# version1.net
KiCad netlist of a schematic drawn in EAGLE
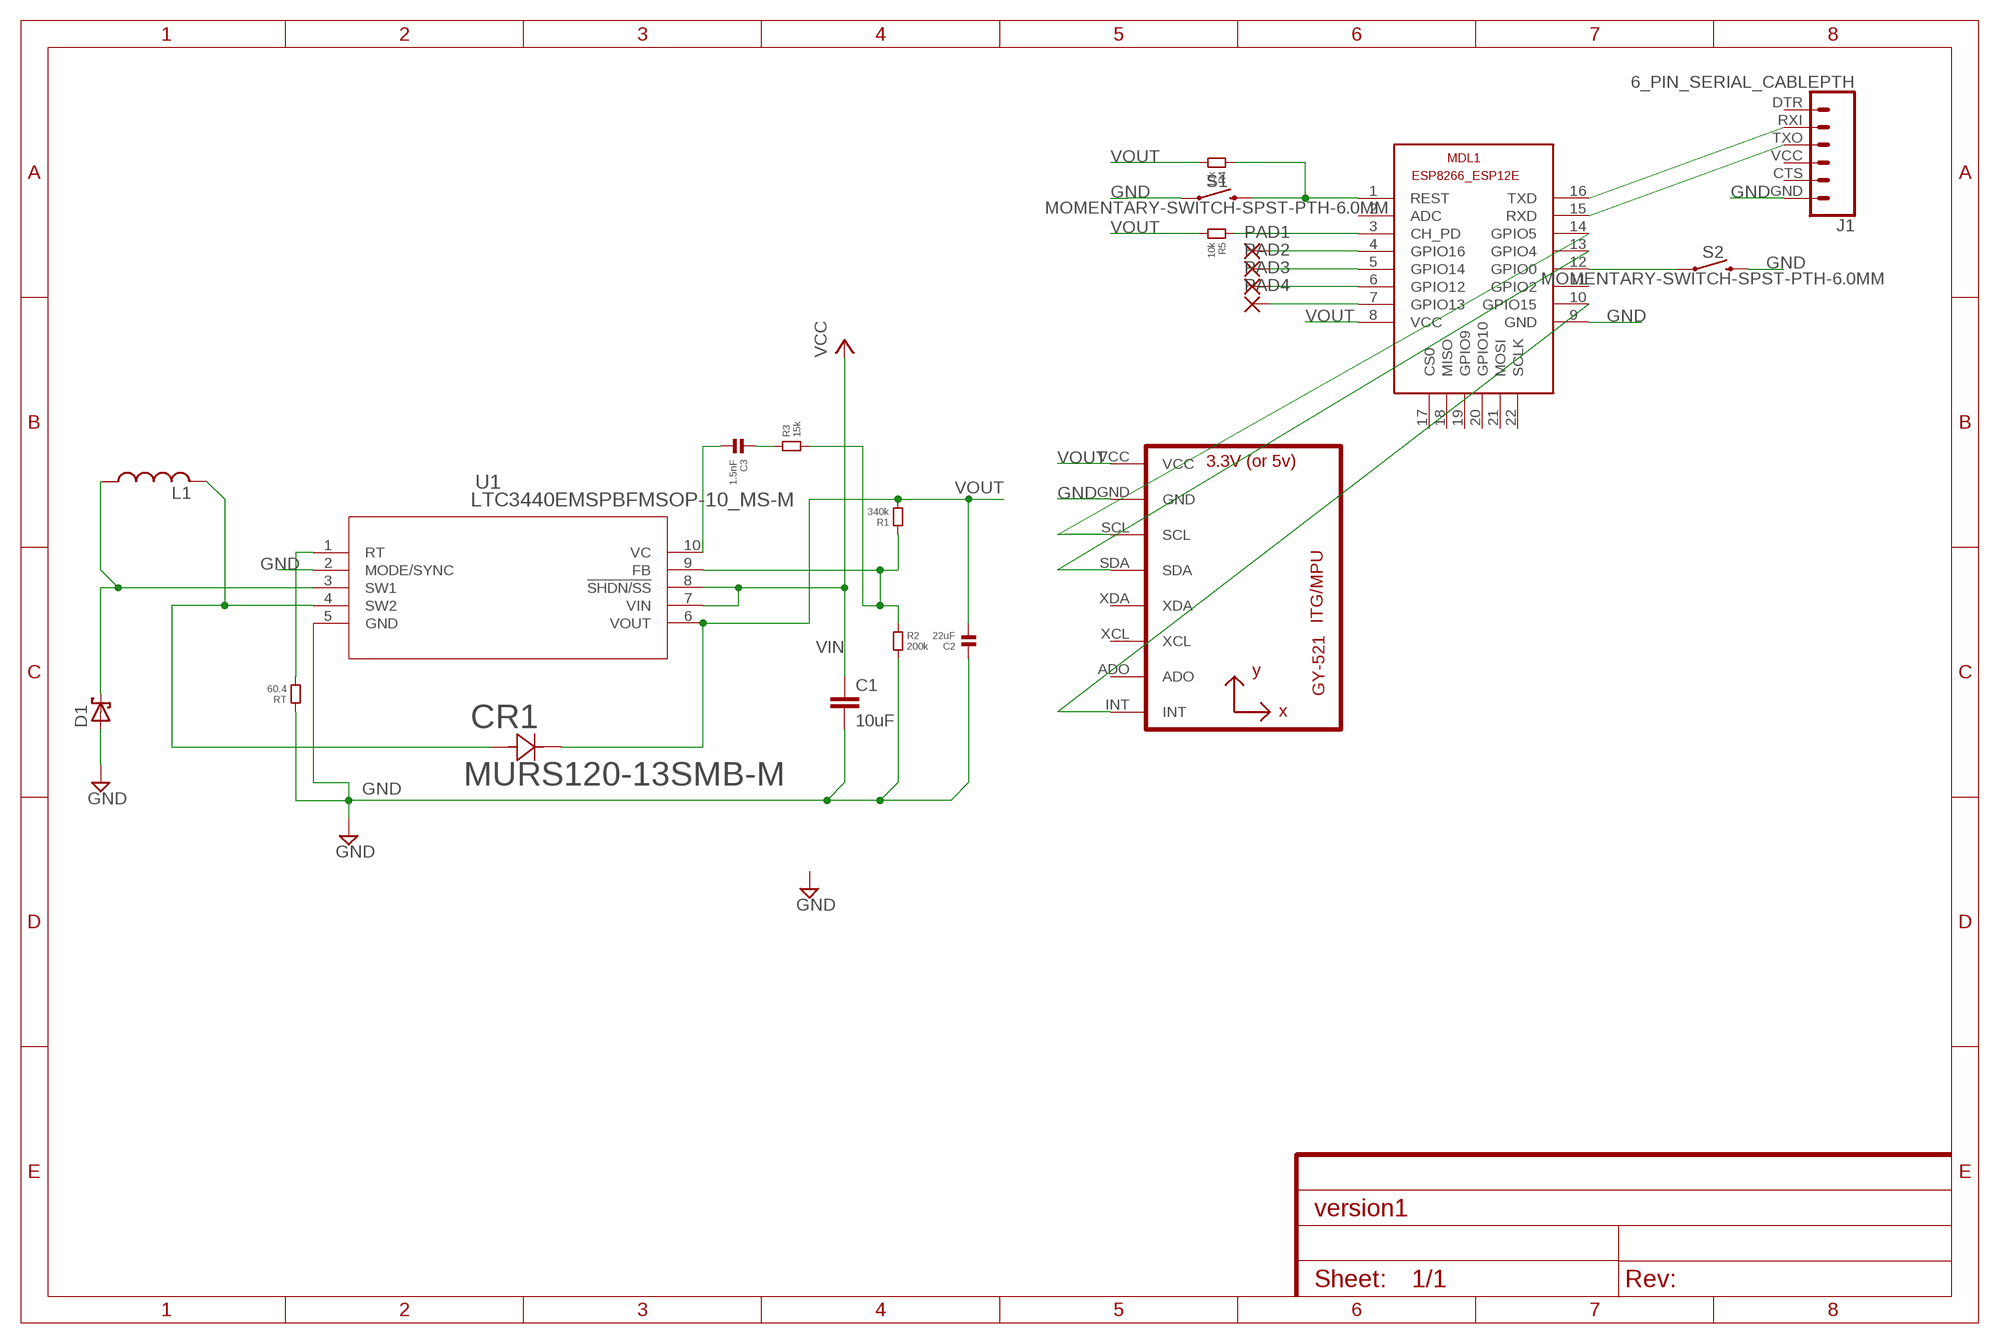
[diagram p0: schematic, sheet 1]

(export (version "E")
  (design (tool "Eeschema 10.0.6"))
  (components
    (comp (ref "C1")
      (value "10uF")
      (footprint "eagle-import:1206")
      (libsource (lib "eagle-import") (part "10UF-1206-6.3V-20%"))
    )
    (comp (ref "C2")
      (value "22uF")
      (footprint "eagle-import:1206")
      (libsource (lib "eagle-import") (part "CAPACITOR.1206"))
    )
    (comp (ref "C3")
      (value "1.5nF")
      (footprint "eagle-import:1206")
      (libsource (lib "eagle-import") (part "CAPACITOR.1206"))
    )
    (comp (ref "CR1")
      (value "MURS120-13SMB-M")
      (footprint "eagle-import:SMB-M")
      (fields (field (name "MANUFACTURER_PART_NUMBER") "MURS12013"))
      (libsource (lib "eagle-import") (part "MURS120-13SMB-M"))
    )
    (comp (ref "D1")
      (value "SCHOTTKY-DIODEDFLS130L-7")
      (footprint "eagle-import:POWERDI-123")
      (fields (field (name "MF") "Diodes Inc") (field (name "MPN") "DFLS130L-7"))
      (libsource (lib "eagle-import") (part "SCHOTTKY-DIODEDFLS130L-7"))
    )
    (comp (ref "J1")
      (value "6_PIN_SERIAL_CABLEPTH")
      (footprint "eagle-import:FTDI_BASIC")
      (libsource (lib "eagle-import") (part "6_PIN_SERIAL_CABLEPTH"))
    )
    (comp (ref "L1")
      (value "INDUCTOR-SUMIDA-CDRH4D18")
      (footprint "eagle-import:INDUCTOR-SUMIDA-CDRH4D18")
      (libsource (lib "eagle-import") (part "INDUCTOR-SUMIDA-CDRH4D18"))
    )
    (comp (ref "MDL1")
      (value "ESP8266-12EESP8266-ESP12E")
      (footprint "eagle-import:ESP8266-ESP12E")
      (libsource (lib "eagle-import") (part "ESP8266-12EESP8266-ESP12E"))
    )
    (comp (ref "PAD1")
      (value "1,6/0,9")
      (footprint "eagle-import:1,6_0,9")
      (libsource (lib "eagle-import") (part "1,6/0,9"))
    )
    (comp (ref "PAD2")
      (value "1,6/0,9")
      (footprint "eagle-import:1,6_0,9")
      (libsource (lib "eagle-import") (part "1,6/0,9"))
    )
    (comp (ref "PAD3")
      (value "1,6/0,9")
      (footprint "eagle-import:1,6_0,9")
      (libsource (lib "eagle-import") (part "1,6/0,9"))
    )
    (comp (ref "PAD4")
      (value "1,6/0,9")
      (footprint "eagle-import:1,6_0,9")
      (libsource (lib "eagle-import") (part "1,6/0,9"))
    )
    (comp (ref "R1")
      (value "340k")
      (footprint "eagle-import:1206")
      (libsource (lib "eagle-import") (part "RESISTOR.1206"))
    )
    (comp (ref "R2")
      (value "200k")
      (footprint "eagle-import:1206")
      (libsource (lib "eagle-import") (part "RESISTOR.1206"))
    )
    (comp (ref "R3")
      (value "15k")
      (footprint "eagle-import:1206")
      (libsource (lib "eagle-import") (part "RESISTOR.1206"))
    )
    (comp (ref "R4")
      (value "10k")
      (footprint "eagle-import:1206")
      (libsource (lib "eagle-import") (part "RESISTOR.1206"))
    )
    (comp (ref "R5")
      (value "10k")
      (footprint "eagle-import:1206")
      (libsource (lib "eagle-import") (part "RESISTOR.1206"))
    )
    (comp (ref "RT")
      (value "60.4")
      (footprint "eagle-import:1206")
      (libsource (lib "eagle-import") (part "RESISTOR.1206"))
    )
    (comp (ref "S1")
      (value "MOMENTARY-SWITCH-SPST-PTH-6.0MM")
      (footprint "eagle-import:TACTILE_SWITCH_PTH_6.0MM")
      (libsource (lib "eagle-import") (part "MOMENTARY-SWITCH-SPST-PTH-6.0MM"))
    )
    (comp (ref "S2")
      (value "MOMENTARY-SWITCH-SPST-PTH-6.0MM")
      (footprint "eagle-import:TACTILE_SWITCH_PTH_6.0MM")
      (libsource (lib "eagle-import") (part "MOMENTARY-SWITCH-SPST-PTH-6.0MM"))
    )
    (comp (ref "U1")
      (value "LTC3440EMSPBFMSOP-10_MS-M")
      (footprint "eagle-import:MSOP-10_MS-M")
      (fields (field (name "MANUFACTURER_PART_NUMBER") "LTC3440EMS#PBF"))
      (libsource (lib "eagle-import") (part "LTC3440EMSPBFMSOP-10_MS-M"))
    )
    (comp (ref "U2")
      (value "GY-521MPU6050")
      (footprint "eagle-import:GY-521")
      (libsource (lib "eagle-import") (part "GY-521MPU6050"))
    )
  )
  (nets
    (net (code "1") (name "/VOUT") (class "Default")
      (node (ref "C2") (pin "2") (pinfunction "2_2") (pintype "bidirectional"))
      (node (ref "CR1") (pin "1") (pinfunction "12_1") (pintype "passive"))
      (node (ref "MDL1") (pin "8") (pinfunction "VCC_8") (pintype "bidirectional"))
      (node (ref "R1") (pin "2") (pinfunction "2_2") (pintype "bidirectional"))
      (node (ref "R4") (pin "2") (pinfunction "2_2") (pintype "bidirectional"))
      (node (ref "R5") (pin "2") (pinfunction "2_2") (pintype "bidirectional"))
      (node (ref "U1") (pin "6") (pinfunction "VOUT_6") (pintype "output"))
      (node (ref "U2") (pin "VCC") (pinfunction "VCC_VCC") (pintype "bidirectional"))
    )
    (net (code "2") (name "GND") (class "Default")
      (node (ref "C1") (pin "2") (pinfunction "2_2") (pintype "passive"))
      (node (ref "C2") (pin "1") (pinfunction "1_1") (pintype "bidirectional"))
      (node (ref "D1") (pin "A") (pinfunction "A_A") (pintype "passive"))
      (node (ref "J1") (pin "GND") (pinfunction "6_GND") (pintype "passive"))
      (node (ref "MDL1") (pin "9") (pinfunction "GND_9") (pintype "bidirectional"))
      (node (ref "R2") (pin "2") (pinfunction "2_2") (pintype "bidirectional"))
      (node (ref "RT") (pin "1") (pinfunction "1_1") (pintype "bidirectional"))
      (node (ref "S1") (pin "1") (pinfunction "1_1") (pintype "passive"))
      (node (ref "S2") (pin "3") (pinfunction "2_3") (pintype "passive"))
      (node (ref "U1") (pin "2") (pinfunction "MODE/SYNC_2") (pintype "input"))
      (node (ref "U1") (pin "5") (pinfunction "GND_5") (pintype "power_in"))
      (node (ref "U2") (pin "GND") (pinfunction "GND_GND") (pintype "bidirectional"))
    )
    (net (code "3") (name "Net-(C3-Pad1)") (class "Default")
      (node (ref "C3") (pin "1") (pinfunction "1_1") (pintype "bidirectional"))
      (node (ref "R3") (pin "1") (pinfunction "1_1") (pintype "bidirectional"))
    )
    (net (code "4") (name "Net-(CR1-21)") (class "Default")
      (node (ref "CR1") (pin "2") (pinfunction "21_2") (pintype "passive"))
      (node (ref "L1") (pin "P$2") (pinfunction "P$2_P$2") (pintype "bidirectional"))
      (node (ref "U1") (pin "4") (pinfunction "SW2_4") (pintype "passive"))
    )
    (net (code "5") (name "Net-(J1-2)") (class "Default")
      (node (ref "J1") (pin "RXI") (pinfunction "2_RXI") (pintype "passive"))
      (node (ref "MDL1") (pin "16") (pinfunction "TXD_16") (pintype "bidirectional"))
    )
    (net (code "6") (name "Net-(J1-3)") (class "Default")
      (node (ref "J1") (pin "TXO") (pinfunction "3_TXO") (pintype "passive"))
      (node (ref "MDL1") (pin "15") (pinfunction "RXD_15") (pintype "bidirectional"))
    )
    (net (code "7") (name "Net-(MDL1-CH_PD)") (class "Default")
      (node (ref "MDL1") (pin "3") (pinfunction "CH_PD_3") (pintype "bidirectional"))
      (node (ref "R5") (pin "1") (pinfunction "1_1") (pintype "bidirectional"))
    )
    (net (code "8") (name "Net-(MDL1-GPIO0)") (class "Default")
      (node (ref "MDL1") (pin "12") (pinfunction "GPIO0_12") (pintype "bidirectional"))
      (node (ref "S2") (pin "1") (pinfunction "1_1") (pintype "passive"))
    )
    (net (code "9") (name "Net-(MDL1-GPIO4)") (class "Default")
      (node (ref "MDL1") (pin "13") (pinfunction "GPIO4_13") (pintype "bidirectional"))
      (node (ref "U2") (pin "SDA") (pinfunction "SDA_SDA") (pintype "bidirectional"))
    )
    (net (code "10") (name "Net-(MDL1-GPIO5)") (class "Default")
      (node (ref "MDL1") (pin "14") (pinfunction "GPIO5_14") (pintype "bidirectional"))
      (node (ref "U2") (pin "SCL") (pinfunction "SCL_SCL") (pintype "bidirectional"))
    )
    (net (code "11") (name "Net-(MDL1-GPIO12)") (class "Default")
      (node (ref "MDL1") (pin "6") (pinfunction "GPIO12_6") (pintype "bidirectional"))
      (node (ref "PAD3") (pin "1") (pinfunction "P_1") (pintype "passive"))
    )
    (net (code "12") (name "Net-(MDL1-GPIO13)") (class "Default")
      (node (ref "MDL1") (pin "7") (pinfunction "GPIO13_7") (pintype "bidirectional"))
      (node (ref "PAD4") (pin "1") (pinfunction "P_1") (pintype "passive"))
    )
    (net (code "13") (name "Net-(MDL1-GPIO14)") (class "Default")
      (node (ref "MDL1") (pin "5") (pinfunction "GPIO14_5") (pintype "bidirectional"))
      (node (ref "PAD2") (pin "1") (pinfunction "P_1") (pintype "passive"))
    )
    (net (code "14") (name "Net-(MDL1-GPIO15)") (class "Default")
      (node (ref "MDL1") (pin "10") (pinfunction "GPIO15_10") (pintype "bidirectional"))
      (node (ref "U2") (pin "INT") (pinfunction "INT_INT") (pintype "bidirectional"))
    )
    (net (code "15") (name "Net-(MDL1-GPIO16)") (class "Default")
      (node (ref "MDL1") (pin "4") (pinfunction "GPIO16_4") (pintype "bidirectional"))
      (node (ref "PAD1") (pin "1") (pinfunction "P_1") (pintype "passive"))
    )
    (net (code "16") (name "Net-(MDL1-REST)") (class "Default")
      (node (ref "MDL1") (pin "1") (pinfunction "REST_1") (pintype "bidirectional"))
      (node (ref "R4") (pin "1") (pinfunction "1_1") (pintype "bidirectional"))
      (node (ref "S1") (pin "3") (pinfunction "2_3") (pintype "passive"))
    )
    (net (code "17") (name "Net-(U1-FB)") (class "Default")
      (node (ref "R1") (pin "1") (pinfunction "1_1") (pintype "bidirectional"))
      (node (ref "R2") (pin "1") (pinfunction "1_1") (pintype "bidirectional"))
      (node (ref "R3") (pin "2") (pinfunction "2_2") (pintype "bidirectional"))
      (node (ref "U1") (pin "9") (pinfunction "FB_9") (pintype "input"))
    )
    (net (code "18") (name "Net-(U1-RT)") (class "Default")
      (node (ref "RT") (pin "2") (pinfunction "2_2") (pintype "bidirectional"))
      (node (ref "U1") (pin "1") (pinfunction "RT_1") (pintype "passive"))
    )
    (net (code "19") (name "Net-(U1-SW1)") (class "Default")
      (node (ref "D1") (pin "C") (pinfunction "C_C") (pintype "passive"))
      (node (ref "L1") (pin "P$1") (pinfunction "P$1_P$1") (pintype "bidirectional"))
      (node (ref "U1") (pin "3") (pinfunction "SW1_3") (pintype "passive"))
    )
    (net (code "20") (name "Net-(U1-VC)") (class "Default")
      (node (ref "C3") (pin "2") (pinfunction "2_2") (pintype "bidirectional"))
      (node (ref "U1") (pin "10") (pinfunction "VC_10") (pintype "output"))
    )
    (net (code "21") (name "VCC") (class "Default")
      (node (ref "C1") (pin "1") (pinfunction "1_1") (pintype "passive"))
      (node (ref "U1") (pin "7") (pinfunction "VIN_7") (pintype "power_in"))
      (node (ref "U1") (pin "8") (pinfunction "~{SHDN/SS}_8") (pintype "input"))
    )
    (net (code "22") (name "unconnected-(J1-1-PadDTR)") (class "Default")
      (node (ref "J1") (pin "DTR") (pinfunction "1_DTR") (pintype "passive"))
    )
    (net (code "23") (name "unconnected-(J1-4-PadVCC)") (class "Default")
      (node (ref "J1") (pin "VCC") (pinfunction "4_VCC") (pintype "passive"))
    )
    (net (code "24") (name "unconnected-(J1-5-PadCTS)") (class "Default")
      (node (ref "J1") (pin "CTS") (pinfunction "5_CTS") (pintype "passive"))
    )
    (net (code "25") (name "unconnected-(MDL1-ADC-Pad2)") (class "Default")
      (node (ref "MDL1") (pin "2") (pinfunction "ADC_2") (pintype "bidirectional"))
    )
    (net (code "26") (name "unconnected-(MDL1-CS0-Pad17)") (class "Default")
      (node (ref "MDL1") (pin "17") (pinfunction "CS0_17") (pintype "bidirectional"))
    )
    (net (code "27") (name "unconnected-(MDL1-GPIO2-Pad11)") (class "Default")
      (node (ref "MDL1") (pin "11") (pinfunction "GPIO2_11") (pintype "bidirectional"))
    )
    (net (code "28") (name "unconnected-(MDL1-GPIO9-Pad19)") (class "Default")
      (node (ref "MDL1") (pin "19") (pinfunction "GPIO9_19") (pintype "bidirectional"))
    )
    (net (code "29") (name "unconnected-(MDL1-GPIO10-Pad20)") (class "Default")
      (node (ref "MDL1") (pin "20") (pinfunction "GPIO10_20") (pintype "bidirectional"))
    )
    (net (code "30") (name "unconnected-(MDL1-MISO-Pad18)") (class "Default")
      (node (ref "MDL1") (pin "18") (pinfunction "MISO_18") (pintype "bidirectional"))
    )
    (net (code "31") (name "unconnected-(MDL1-MOSI-Pad21)") (class "Default")
      (node (ref "MDL1") (pin "21") (pinfunction "MOSI_21") (pintype "bidirectional"))
    )
    (net (code "32") (name "unconnected-(MDL1-SCLK-Pad22)") (class "Default")
      (node (ref "MDL1") (pin "22") (pinfunction "SCLK_22") (pintype "bidirectional"))
    )
    (net (code "33") (name "unconnected-(U2-PadADO)") (class "Default")
      (node (ref "U2") (pin "ADO") (pinfunction "ADO_ADO") (pintype "bidirectional"))
    )
    (net (code "34") (name "unconnected-(U2-PadXCL)") (class "Default")
      (node (ref "U2") (pin "XCL") (pinfunction "XCL_XCL") (pintype "bidirectional"))
    )
    (net (code "35") (name "unconnected-(U2-PadXDA)") (class "Default")
      (node (ref "U2") (pin "XDA") (pinfunction "XDA_XDA") (pintype "bidirectional"))
    )
  )
)
